# AS3364_DG412_bus_mixer_v1_1.net
KiCad netlist of a schematic drawn in EAGLE
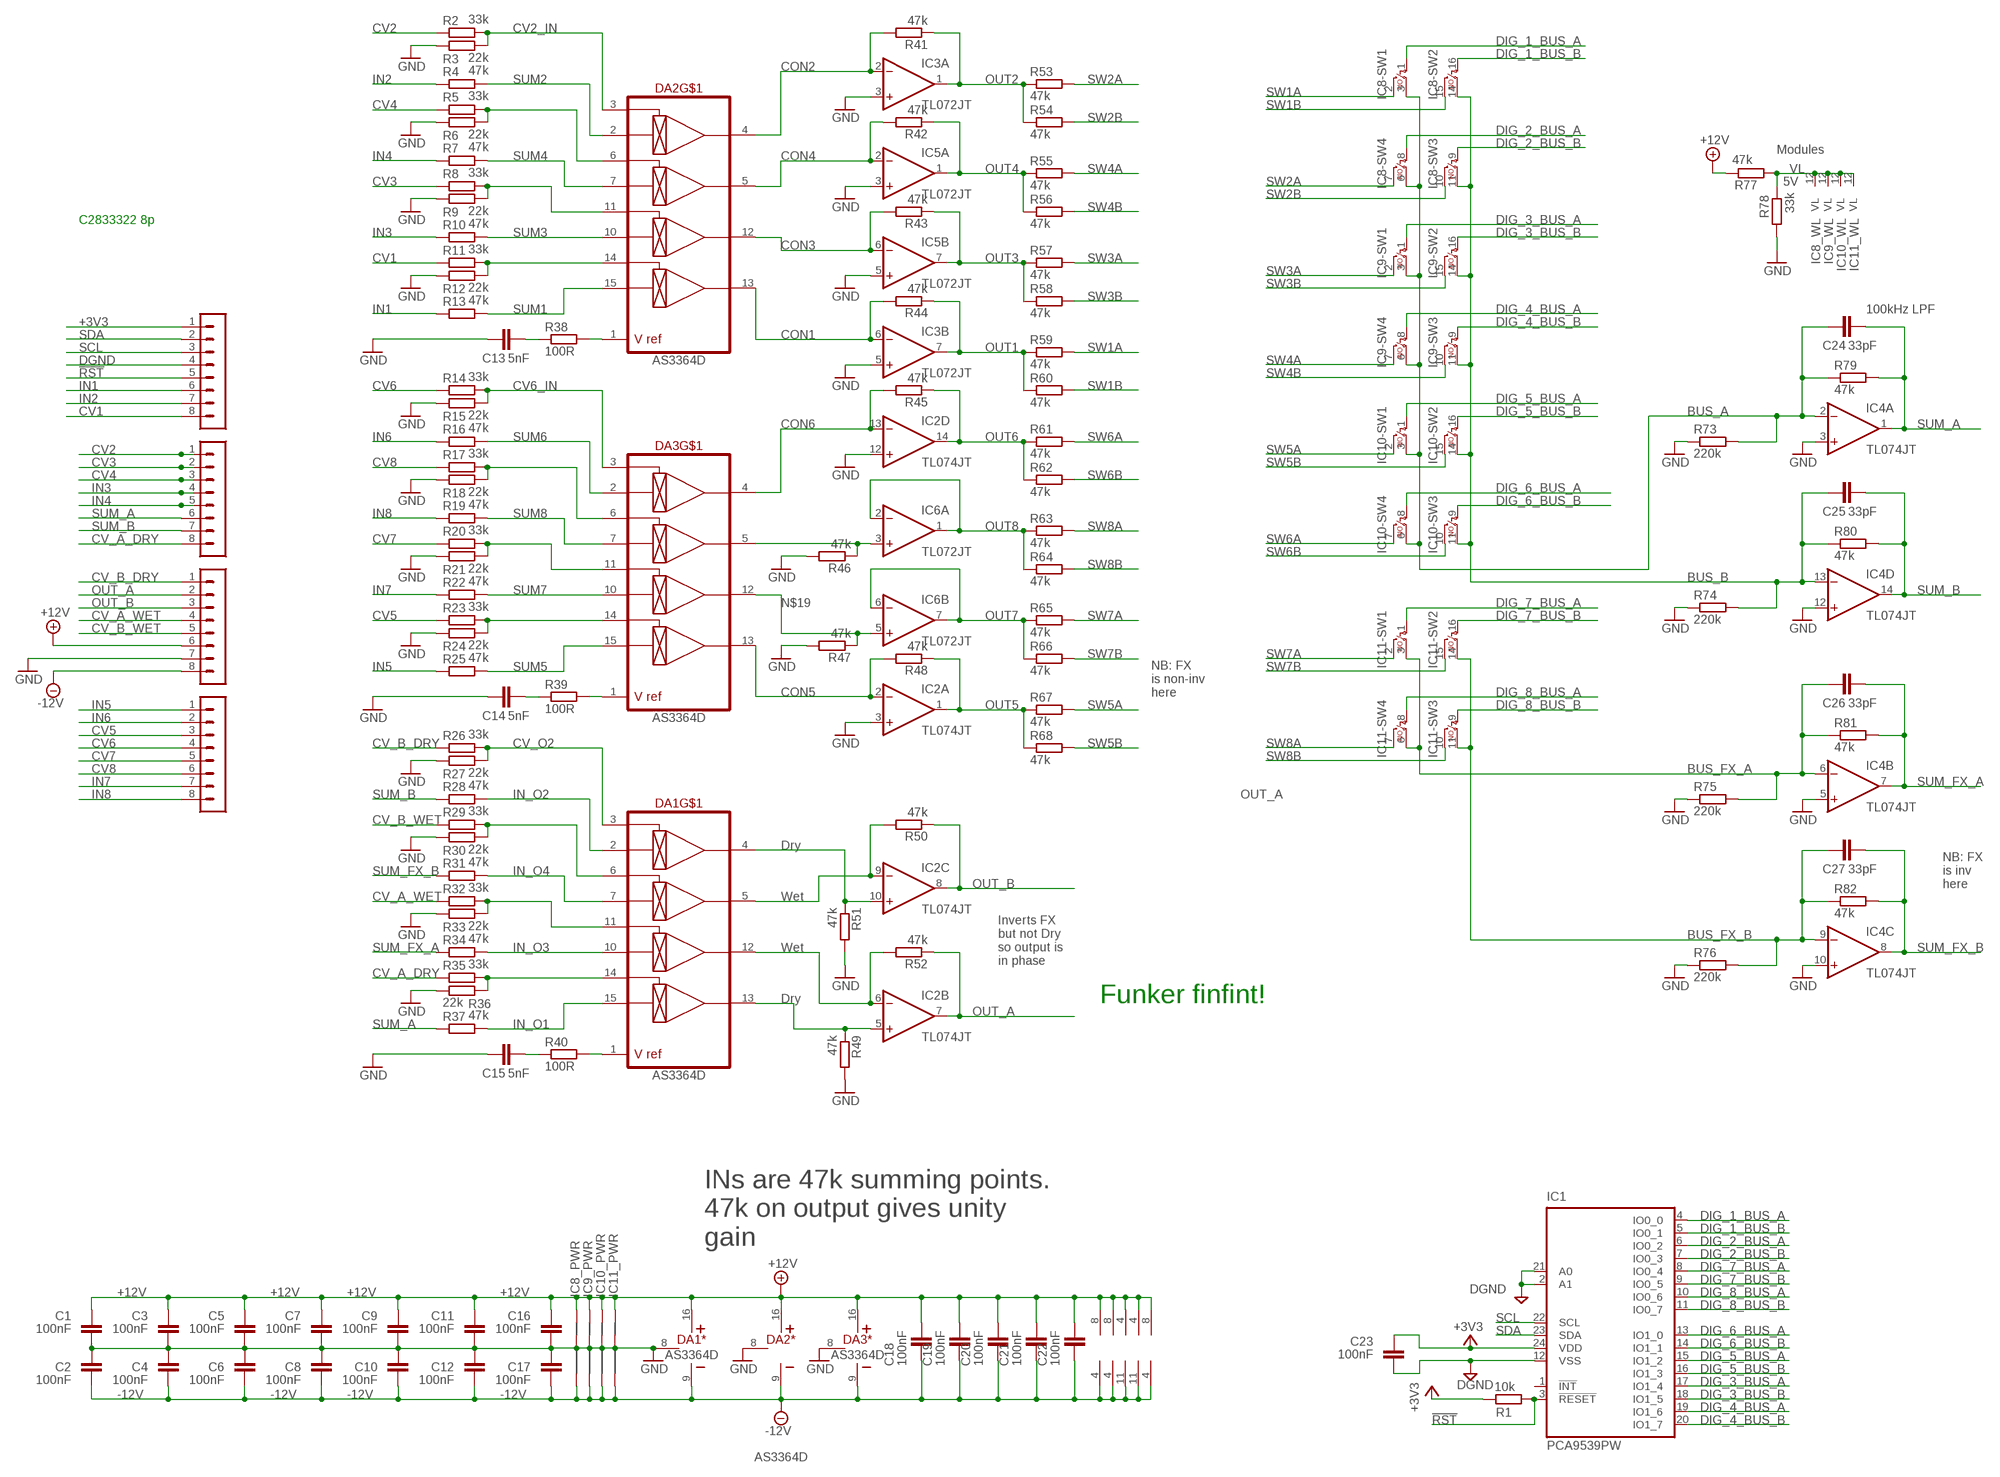
[diagram p0: schematic, sheet 1]

(export (version "E")
  (design (tool "Eeschema 10.0.6"))
  (components
    (comp (ref "C1")
      (value "100nF")
      (footprint "eagle-import:C0402")
      (libsource (lib "eagle-import") (part "C-EUC0402"))
    )
    (comp (ref "C2")
      (value "100nF")
      (footprint "eagle-import:C0402")
      (libsource (lib "eagle-import") (part "C-EUC0402"))
    )
    (comp (ref "C3")
      (value "100nF")
      (footprint "eagle-import:C0402")
      (libsource (lib "eagle-import") (part "C-EUC0402"))
    )
    (comp (ref "C4")
      (value "100nF")
      (footprint "eagle-import:C0402")
      (libsource (lib "eagle-import") (part "C-EUC0402"))
    )
    (comp (ref "C5")
      (value "100nF")
      (footprint "eagle-import:C0402")
      (libsource (lib "eagle-import") (part "C-EUC0402"))
    )
    (comp (ref "C6")
      (value "100nF")
      (footprint "eagle-import:C0402")
      (libsource (lib "eagle-import") (part "C-EUC0402"))
    )
    (comp (ref "C7")
      (value "100nF")
      (footprint "eagle-import:C0402")
      (libsource (lib "eagle-import") (part "C-EUC0402"))
    )
    (comp (ref "C8")
      (value "100nF")
      (footprint "eagle-import:C0402")
      (libsource (lib "eagle-import") (part "C-EUC0402"))
    )
    (comp (ref "C9")
      (value "100nF")
      (footprint "eagle-import:C0402")
      (libsource (lib "eagle-import") (part "C-EUC0402"))
    )
    (comp (ref "C10")
      (value "100nF")
      (footprint "eagle-import:C0402")
      (libsource (lib "eagle-import") (part "C-EUC0402"))
    )
    (comp (ref "C11")
      (value "100nF")
      (footprint "eagle-import:C0402")
      (libsource (lib "eagle-import") (part "C-EUC0402"))
    )
    (comp (ref "C12")
      (value "100nF")
      (footprint "eagle-import:C0402")
      (libsource (lib "eagle-import") (part "C-EUC0402"))
    )
    (comp (ref "C13")
      (value "5nF")
      (footprint "eagle-import:C0402-J")
      (libsource (lib "eagle-import") (part "C-EU-J"))
    )
    (comp (ref "C14")
      (value "5nF")
      (footprint "eagle-import:C0402-J")
      (libsource (lib "eagle-import") (part "C-EU-J"))
    )
    (comp (ref "C15")
      (value "5nF")
      (footprint "eagle-import:C0402-J")
      (libsource (lib "eagle-import") (part "C-EU-J"))
    )
    (comp (ref "C16")
      (value "100nF")
      (footprint "eagle-import:C0402")
      (libsource (lib "eagle-import") (part "C-EUC0402"))
    )
    (comp (ref "C17")
      (value "100nF")
      (footprint "eagle-import:C0402")
      (libsource (lib "eagle-import") (part "C-EUC0402"))
    )
    (comp (ref "C18")
      (value "100nF")
      (footprint "eagle-import:C0402")
      (libsource (lib "eagle-import") (part "C-EUC0402"))
    )
    (comp (ref "C19")
      (value "100nF")
      (footprint "eagle-import:C0402")
      (libsource (lib "eagle-import") (part "C-EUC0402"))
    )
    (comp (ref "C20")
      (value "100nF")
      (footprint "eagle-import:C0402")
      (libsource (lib "eagle-import") (part "C-EUC0402"))
    )
    (comp (ref "C21")
      (value "100nF")
      (footprint "eagle-import:C0402")
      (libsource (lib "eagle-import") (part "C-EUC0402"))
    )
    (comp (ref "C22")
      (value "100nF")
      (footprint "eagle-import:C0402")
      (libsource (lib "eagle-import") (part "C-EUC0402"))
    )
    (comp (ref "C23")
      (value "100nF")
      (footprint "eagle-import:C0402")
      (libsource (lib "eagle-import") (part "C-EUC0402"))
    )
    (comp (ref "C24")
      (value "33pF")
      (footprint "eagle-import:C0402-J")
      (libsource (lib "eagle-import") (part "C-EU-J"))
    )
    (comp (ref "C25")
      (value "33pF")
      (footprint "eagle-import:C0402-J")
      (libsource (lib "eagle-import") (part "C-EU-J"))
    )
    (comp (ref "C26")
      (value "33pF")
      (footprint "eagle-import:C0402-J")
      (libsource (lib "eagle-import") (part "C-EU-J"))
    )
    (comp (ref "C27")
      (value "33pF")
      (footprint "eagle-import:C0402-J")
      (libsource (lib "eagle-import") (part "C-EU-J"))
    )
    (comp (ref "DA1")
      (value "AS3364D")
      (footprint "eagle-import:DIL16J")
      (libsource (lib "eagle-import") (part "AS3364D"))
    )
    (comp (ref "DA2")
      (value "AS3364D")
      (footprint "eagle-import:DIL16J")
      (libsource (lib "eagle-import") (part "AS3364D"))
    )
    (comp (ref "DA3")
      (value "AS3364D")
      (footprint "eagle-import:DIL16J")
      (libsource (lib "eagle-import") (part "AS3364D"))
    )
    (comp (ref "IC1")
      (value "PCA9539PW")
      (footprint "eagle-import:TSSOP24J")
      (libsource (lib "eagle-import") (part "PCA9539PW"))
    )
    (comp (ref "IC2")
      (value "TL074JT")
      (footprint "eagle-import:TSSOP14J")
      (libsource (lib "eagle-import") (part "TL074JT"))
    )
    (comp (ref "IC3")
      (value "TL072JT")
      (footprint "eagle-import:TSSOP8J")
      (libsource (lib "eagle-import") (part "TL072JT"))
    )
    (comp (ref "IC4")
      (value "TL074JT")
      (footprint "eagle-import:TSSOP14J")
      (libsource (lib "eagle-import") (part "TL074JT"))
    )
    (comp (ref "IC5")
      (value "TL072JT")
      (footprint "eagle-import:TSSOP8J")
      (libsource (lib "eagle-import") (part "TL072JT"))
    )
    (comp (ref "IC6")
      (value "TL072JT")
      (footprint "eagle-import:TSSOP8J")
      (libsource (lib "eagle-import") (part "TL072JT"))
    )
    (comp (ref "IC8")
      (value "DG412-J")
      (footprint "eagle-import:DIL16J")
      (libsource (lib "eagle-import") (part "DG412-J"))
    )
    (comp (ref "IC9")
      (value "DG412-J")
      (footprint "eagle-import:DIL16J")
      (libsource (lib "eagle-import") (part "DG412-J"))
    )
    (comp (ref "IC10")
      (value "DG412-J")
      (footprint "eagle-import:DIL16J")
      (libsource (lib "eagle-import") (part "DG412-J"))
    )
    (comp (ref "IC11")
      (value "DG412-J")
      (footprint "eagle-import:DIL16J")
      (libsource (lib "eagle-import") (part "DG412-J"))
    )
    (comp (ref "R1")
      (value "10k")
      (footprint "eagle-import:R0402")
      (libsource (lib "eagle-import") (part "R-EU_R0402"))
    )
    (comp (ref "R2")
      (value "33k")
      (footprint "eagle-import:R0402")
      (libsource (lib "eagle-import") (part "R-EU_R0402"))
    )
    (comp (ref "R3")
      (value "22k")
      (footprint "eagle-import:R0402")
      (libsource (lib "eagle-import") (part "R-EU_R0402"))
    )
    (comp (ref "R4")
      (value "47k")
      (footprint "eagle-import:R0402")
      (libsource (lib "eagle-import") (part "R-EU_R0402"))
    )
    (comp (ref "R5")
      (value "33k")
      (footprint "eagle-import:R0402")
      (libsource (lib "eagle-import") (part "R-EU_R0402"))
    )
    (comp (ref "R6")
      (value "22k")
      (footprint "eagle-import:R0402")
      (libsource (lib "eagle-import") (part "R-EU_R0402"))
    )
    (comp (ref "R7")
      (value "47k")
      (footprint "eagle-import:R0402")
      (libsource (lib "eagle-import") (part "R-EU_R0402"))
    )
    (comp (ref "R8")
      (value "33k")
      (footprint "eagle-import:R0402")
      (libsource (lib "eagle-import") (part "R-EU_R0402"))
    )
    (comp (ref "R9")
      (value "22k")
      (footprint "eagle-import:R0402")
      (libsource (lib "eagle-import") (part "R-EU_R0402"))
    )
    (comp (ref "R10")
      (value "47k")
      (footprint "eagle-import:R0402")
      (libsource (lib "eagle-import") (part "R-EU_R0402"))
    )
    (comp (ref "R11")
      (value "33k")
      (footprint "eagle-import:R0402")
      (libsource (lib "eagle-import") (part "R-EU_R0402"))
    )
    (comp (ref "R12")
      (value "22k")
      (footprint "eagle-import:R0402")
      (libsource (lib "eagle-import") (part "R-EU_R0402"))
    )
    (comp (ref "R13")
      (value "47k")
      (footprint "eagle-import:R0402")
      (libsource (lib "eagle-import") (part "R-EU_R0402"))
    )
    (comp (ref "R14")
      (value "33k")
      (footprint "eagle-import:R0402")
      (libsource (lib "eagle-import") (part "R-EU_R0402"))
    )
    (comp (ref "R15")
      (value "22k")
      (footprint "eagle-import:R0402")
      (libsource (lib "eagle-import") (part "R-EU_R0402"))
    )
    (comp (ref "R16")
      (value "47k")
      (footprint "eagle-import:R0402")
      (libsource (lib "eagle-import") (part "R-EU_R0402"))
    )
    (comp (ref "R17")
      (value "33k")
      (footprint "eagle-import:R0402")
      (libsource (lib "eagle-import") (part "R-EU_R0402"))
    )
    (comp (ref "R18")
      (value "22k")
      (footprint "eagle-import:R0402")
      (libsource (lib "eagle-import") (part "R-EU_R0402"))
    )
    (comp (ref "R19")
      (value "47k")
      (footprint "eagle-import:R0402")
      (libsource (lib "eagle-import") (part "R-EU_R0402"))
    )
    (comp (ref "R20")
      (value "33k")
      (footprint "eagle-import:R0402")
      (libsource (lib "eagle-import") (part "R-EU_R0402"))
    )
    (comp (ref "R21")
      (value "22k")
      (footprint "eagle-import:R0402")
      (libsource (lib "eagle-import") (part "R-EU_R0402"))
    )
    (comp (ref "R22")
      (value "47k")
      (footprint "eagle-import:R0402")
      (libsource (lib "eagle-import") (part "R-EU_R0402"))
    )
    (comp (ref "R23")
      (value "33k")
      (footprint "eagle-import:R0402")
      (libsource (lib "eagle-import") (part "R-EU_R0402"))
    )
    (comp (ref "R24")
      (value "22k")
      (footprint "eagle-import:R0402")
      (libsource (lib "eagle-import") (part "R-EU_R0402"))
    )
    (comp (ref "R25")
      (value "47k")
      (footprint "eagle-import:R0402")
      (libsource (lib "eagle-import") (part "R-EU_R0402"))
    )
    (comp (ref "R26")
      (value "33k")
      (footprint "eagle-import:R0402")
      (libsource (lib "eagle-import") (part "R-EU_R0402"))
    )
    (comp (ref "R27")
      (value "22k")
      (footprint "eagle-import:R0402")
      (libsource (lib "eagle-import") (part "R-EU_R0402"))
    )
    (comp (ref "R28")
      (value "47k")
      (footprint "eagle-import:R0402")
      (libsource (lib "eagle-import") (part "R-EU_R0402"))
    )
    (comp (ref "R29")
      (value "33k")
      (footprint "eagle-import:R0402")
      (libsource (lib "eagle-import") (part "R-EU_R0402"))
    )
    (comp (ref "R30")
      (value "22k")
      (footprint "eagle-import:R0402")
      (libsource (lib "eagle-import") (part "R-EU_R0402"))
    )
    (comp (ref "R31")
      (value "47k")
      (footprint "eagle-import:R0402")
      (libsource (lib "eagle-import") (part "R-EU_R0402"))
    )
    (comp (ref "R32")
      (value "33k")
      (footprint "eagle-import:R0402")
      (libsource (lib "eagle-import") (part "R-EU_R0402"))
    )
    (comp (ref "R33")
      (value "22k")
      (footprint "eagle-import:R0402")
      (libsource (lib "eagle-import") (part "R-EU_R0402"))
    )
    (comp (ref "R34")
      (value "47k")
      (footprint "eagle-import:R0402")
      (libsource (lib "eagle-import") (part "R-EU_R0402"))
    )
    (comp (ref "R35")
      (value "33k")
      (footprint "eagle-import:R0402")
      (libsource (lib "eagle-import") (part "R-EU_R0402"))
    )
    (comp (ref "R36")
      (value "22k")
      (footprint "eagle-import:R0402")
      (libsource (lib "eagle-import") (part "R-EU_R0402"))
    )
    (comp (ref "R37")
      (value "47k")
      (footprint "eagle-import:R0402")
      (libsource (lib "eagle-import") (part "R-EU_R0402"))
    )
    (comp (ref "R38")
      (value "100R")
      (footprint "eagle-import:R0402")
      (libsource (lib "eagle-import") (part "R-EU_R0402"))
    )
    (comp (ref "R39")
      (value "100R")
      (footprint "eagle-import:R0402")
      (libsource (lib "eagle-import") (part "R-EU_R0402"))
    )
    (comp (ref "R40")
      (value "100R")
      (footprint "eagle-import:R0402")
      (libsource (lib "eagle-import") (part "R-EU_R0402"))
    )
    (comp (ref "R41")
      (value "47k")
      (footprint "eagle-import:R0402")
      (libsource (lib "eagle-import") (part "R-EU_R0402"))
    )
    (comp (ref "R42")
      (value "47k")
      (footprint "eagle-import:R0402")
      (libsource (lib "eagle-import") (part "R-EU_R0402"))
    )
    (comp (ref "R43")
      (value "47k")
      (footprint "eagle-import:R0402")
      (libsource (lib "eagle-import") (part "R-EU_R0402"))
    )
    (comp (ref "R44")
      (value "47k")
      (footprint "eagle-import:R0402")
      (libsource (lib "eagle-import") (part "R-EU_R0402"))
    )
    (comp (ref "R45")
      (value "47k")
      (footprint "eagle-import:R0402")
      (libsource (lib "eagle-import") (part "R-EU_R0402"))
    )
    (comp (ref "R46")
      (value "47k")
      (footprint "eagle-import:R0402")
      (libsource (lib "eagle-import") (part "R-EU_R0402"))
    )
    (comp (ref "R47")
      (value "47k")
      (footprint "eagle-import:R0402")
      (libsource (lib "eagle-import") (part "R-EU_R0402"))
    )
    (comp (ref "R48")
      (value "47k")
      (footprint "eagle-import:R0402")
      (libsource (lib "eagle-import") (part "R-EU_R0402"))
    )
    (comp (ref "R49")
      (value "47k")
      (footprint "eagle-import:R0402")
      (libsource (lib "eagle-import") (part "R-EU_R0402"))
    )
    (comp (ref "R50")
      (value "47k")
      (footprint "eagle-import:R0402")
      (libsource (lib "eagle-import") (part "R-EU_R0402"))
    )
    (comp (ref "R51")
      (value "47k")
      (footprint "eagle-import:R0402")
      (libsource (lib "eagle-import") (part "R-EU_R0402"))
    )
    (comp (ref "R52")
      (value "47k")
      (footprint "eagle-import:R0402")
      (libsource (lib "eagle-import") (part "R-EU_R0402"))
    )
    (comp (ref "R53")
      (value "47k")
      (footprint "eagle-import:R0402")
      (libsource (lib "eagle-import") (part "R-EU_R0402"))
    )
    (comp (ref "R54")
      (value "47k")
      (footprint "eagle-import:R0402")
      (libsource (lib "eagle-import") (part "R-EU_R0402"))
    )
    (comp (ref "R55")
      (value "47k")
      (footprint "eagle-import:R0402")
      (libsource (lib "eagle-import") (part "R-EU_R0402"))
    )
    (comp (ref "R56")
      (value "47k")
      (footprint "eagle-import:R0402")
      (libsource (lib "eagle-import") (part "R-EU_R0402"))
    )
    (comp (ref "R57")
      (value "47k")
      (footprint "eagle-import:R0402")
      (libsource (lib "eagle-import") (part "R-EU_R0402"))
    )
    (comp (ref "R58")
      (value "47k")
      (footprint "eagle-import:R0402")
      (libsource (lib "eagle-import") (part "R-EU_R0402"))
    )
    (comp (ref "R59")
      (value "47k")
      (footprint "eagle-import:R0402")
      (libsource (lib "eagle-import") (part "R-EU_R0402"))
    )
    (comp (ref "R60")
      (value "47k")
      (footprint "eagle-import:R0402")
      (libsource (lib "eagle-import") (part "R-EU_R0402"))
    )
    (comp (ref "R61")
      (value "47k")
      (footprint "eagle-import:R0402")
      (libsource (lib "eagle-import") (part "R-EU_R0402"))
    )
    (comp (ref "R62")
      (value "47k")
      (footprint "eagle-import:R0402")
      (libsource (lib "eagle-import") (part "R-EU_R0402"))
    )
    (comp (ref "R63")
      (value "47k")
      (footprint "eagle-import:R0402")
      (libsource (lib "eagle-import") (part "R-EU_R0402"))
    )
    (comp (ref "R64")
      (value "47k")
      (footprint "eagle-import:R0402")
      (libsource (lib "eagle-import") (part "R-EU_R0402"))
    )
    (comp (ref "R65")
      (value "47k")
      (footprint "eagle-import:R0402")
      (libsource (lib "eagle-import") (part "R-EU_R0402"))
    )
    (comp (ref "R66")
      (value "47k")
      (footprint "eagle-import:R0402")
      (libsource (lib "eagle-import") (part "R-EU_R0402"))
    )
    (comp (ref "R67")
      (value "47k")
      (footprint "eagle-import:R0402")
      (libsource (lib "eagle-import") (part "R-EU_R0402"))
    )
    (comp (ref "R68")
      (value "47k")
      (footprint "eagle-import:R0402")
      (libsource (lib "eagle-import") (part "R-EU_R0402"))
    )
    (comp (ref "R73")
      (value "220k")
      (footprint "eagle-import:R0402")
      (libsource (lib "eagle-import") (part "R-EU_R0402"))
    )
    (comp (ref "R74")
      (value "220k")
      (footprint "eagle-import:R0402")
      (libsource (lib "eagle-import") (part "R-EU_R0402"))
    )
    (comp (ref "R75")
      (value "220k")
      (footprint "eagle-import:R0402")
      (libsource (lib "eagle-import") (part "R-EU_R0402"))
    )
    (comp (ref "R76")
      (value "220k")
      (footprint "eagle-import:R0402")
      (libsource (lib "eagle-import") (part "R-EU_R0402"))
    )
    (comp (ref "R77")
      (value "47k")
      (footprint "eagle-import:R0402")
      (libsource (lib "eagle-import") (part "R-EU_R0402"))
    )
    (comp (ref "R78")
      (value "33k")
      (footprint "eagle-import:R0402")
      (libsource (lib "eagle-import") (part "R-EU_R0402"))
    )
    (comp (ref "R79")
      (value "47k")
      (footprint "eagle-import:R0402")
      (libsource (lib "eagle-import") (part "R-EU_R0402"))
    )
    (comp (ref "R80")
      (value "47k")
      (footprint "eagle-import:R0402")
      (libsource (lib "eagle-import") (part "R-EU_R0402"))
    )
    (comp (ref "R81")
      (value "47k")
      (footprint "eagle-import:R0402")
      (libsource (lib "eagle-import") (part "R-EU_R0402"))
    )
    (comp (ref "R82")
      (value "47k")
      (footprint "eagle-import:R0402")
      (libsource (lib "eagle-import") (part "R-EU_R0402"))
    )
    (comp (ref "SV1")
      (value "MA08-1JP")
      (footprint "eagle-import:SIP-PIN08-1J")
      (libsource (lib "eagle-import") (part "MA08-1JP"))
    )
    (comp (ref "SV3")
      (value "MA08-1JP")
      (footprint "eagle-import:SIP-PIN08-1J")
      (libsource (lib "eagle-import") (part "MA08-1JP"))
    )
    (comp (ref "SV4")
      (value "MA08-1JP")
      (footprint "eagle-import:SIP-PIN08-1J")
      (libsource (lib "eagle-import") (part "MA08-1JP"))
    )
    (comp (ref "SV33")
      (value "MA08-1JP")
      (footprint "eagle-import:SIP-PIN08-1J")
      (libsource (lib "eagle-import") (part "MA08-1JP"))
    )
  )
  (nets
    (net (code "1") (name "+3V3") (class "Default")
      (node (ref "C23") (pin "2") (pinfunction "2_2") (pintype "passive"))
      (node (ref "IC1") (pin "24") (pinfunction "VDD_24") (pintype "power_in"))
      (node (ref "R1") (pin "1") (pinfunction "1_1") (pintype "passive"))
      (node (ref "SV33") (pin "1") (pinfunction "1_1") (pintype "passive"))
    )
    (net (code "2") (name "+12V") (class "Default")
      (node (ref "C1") (pin "2") (pinfunction "2_2") (pintype "passive"))
      (node (ref "C11") (pin "2") (pinfunction "2_2") (pintype "passive"))
      (node (ref "C16") (pin "2") (pinfunction "2_2") (pintype "passive"))
      (node (ref "C18") (pin "2") (pinfunction "2_2") (pintype "passive"))
      (node (ref "C19") (pin "2") (pinfunction "2_2") (pintype "passive"))
      (node (ref "C20") (pin "2") (pinfunction "2_2") (pintype "passive"))
      (node (ref "C21") (pin "2") (pinfunction "2_2") (pintype "passive"))
      (node (ref "C22") (pin "2") (pinfunction "2_2") (pintype "passive"))
      (node (ref "C3") (pin "2") (pinfunction "2_2") (pintype "passive"))
      (node (ref "C5") (pin "2") (pinfunction "2_2") (pintype "passive"))
      (node (ref "C7") (pin "2") (pinfunction "2_2") (pintype "passive"))
      (node (ref "C9") (pin "2") (pinfunction "2_2") (pintype "passive"))
      (node (ref "DA1") (pin "16") (pinfunction "V+_16") (pintype "power_in"))
      (node (ref "DA2") (pin "16") (pinfunction "V+_16") (pintype "power_in"))
      (node (ref "DA3") (pin "16") (pinfunction "V+_16") (pintype "power_in"))
      (node (ref "IC10") (pin "13") (pinfunction "+15V_13") (pintype "power_in"))
      (node (ref "IC11") (pin "13") (pinfunction "+15V_13") (pintype "power_in"))
      (node (ref "IC2") (pin "4") (pinfunction "V+_4") (pintype "power_in"))
      (node (ref "IC3") (pin "8") (pinfunction "V+_8") (pintype "power_in"))
      (node (ref "IC4") (pin "4") (pinfunction "V+_4") (pintype "power_in"))
      (node (ref "IC5") (pin "8") (pinfunction "V+_8") (pintype "power_in"))
      (node (ref "IC6") (pin "8") (pinfunction "V+_8") (pintype "power_in"))
      (node (ref "IC8") (pin "13") (pinfunction "+15V_13") (pintype "power_in"))
      (node (ref "IC9") (pin "13") (pinfunction "+15V_13") (pintype "power_in"))
      (node (ref "R77") (pin "1") (pinfunction "1_1") (pintype "passive"))
      (node (ref "SV4") (pin "6") (pinfunction "6_6") (pintype "passive"))
    )
    (net (code "3") (name "-12V") (class "Default")
      (node (ref "C10") (pin "1") (pinfunction "1_1") (pintype "passive"))
      (node (ref "C12") (pin "1") (pinfunction "1_1") (pintype "passive"))
      (node (ref "C17") (pin "1") (pinfunction "1_1") (pintype "passive"))
      (node (ref "C18") (pin "1") (pinfunction "1_1") (pintype "passive"))
      (node (ref "C19") (pin "1") (pinfunction "1_1") (pintype "passive"))
      (node (ref "C2") (pin "1") (pinfunction "1_1") (pintype "passive"))
      (node (ref "C20") (pin "1") (pinfunction "1_1") (pintype "passive"))
      (node (ref "C21") (pin "1") (pinfunction "1_1") (pintype "passive"))
      (node (ref "C22") (pin "1") (pinfunction "1_1") (pintype "passive"))
      (node (ref "C4") (pin "1") (pinfunction "1_1") (pintype "passive"))
      (node (ref "C6") (pin "1") (pinfunction "1_1") (pintype "passive"))
      (node (ref "C8") (pin "1") (pinfunction "1_1") (pintype "passive"))
      (node (ref "DA1") (pin "9") (pinfunction "V-_9") (pintype "power_in"))
      (node (ref "DA2") (pin "9") (pinfunction "V-_9") (pintype "power_in"))
      (node (ref "DA3") (pin "9") (pinfunction "V-_9") (pintype "power_in"))
      (node (ref "IC10") (pin "4") (pinfunction "-15V_4") (pintype "power_in"))
      (node (ref "IC11") (pin "4") (pinfunction "-15V_4") (pintype "power_in"))
      (node (ref "IC2") (pin "11") (pinfunction "V-_11") (pintype "power_in"))
      (node (ref "IC3") (pin "4") (pinfunction "V-_4") (pintype "power_in"))
      (node (ref "IC4") (pin "11") (pinfunction "V-_11") (pintype "power_in"))
      (node (ref "IC5") (pin "4") (pinfunction "V-_4") (pintype "power_in"))
      (node (ref "IC6") (pin "4") (pinfunction "V-_4") (pintype "power_in"))
      (node (ref "IC8") (pin "4") (pinfunction "-15V_4") (pintype "power_in"))
      (node (ref "IC9") (pin "4") (pinfunction "-15V_4") (pintype "power_in"))
      (node (ref "SV4") (pin "8") (pinfunction "8_8") (pintype "passive"))
    )
    (net (code "4") (name "/BUS_A") (class "Default")
      (node (ref "C24") (pin "1") (pinfunction "1_1") (pintype "passive"))
      (node (ref "IC10") (pin "3") (pinfunction "S_3") (pintype "bidirectional"))
      (node (ref "IC10") (pin "6") (pinfunction "S_6") (pintype "bidirectional"))
      (node (ref "IC4") (pin "2") (pinfunction "-IN_2") (pintype "input"))
      (node (ref "IC8") (pin "3") (pinfunction "S_3") (pintype "bidirectional"))
      (node (ref "IC8") (pin "6") (pinfunction "S_6") (pintype "bidirectional"))
      (node (ref "IC9") (pin "3") (pinfunction "S_3") (pintype "bidirectional"))
      (node (ref "IC9") (pin "6") (pinfunction "S_6") (pintype "bidirectional"))
      (node (ref "R73") (pin "2") (pinfunction "2_2") (pintype "passive"))
      (node (ref "R79") (pin "1") (pinfunction "1_1") (pintype "passive"))
    )
    (net (code "5") (name "/BUS_B") (class "Default")
      (node (ref "C25") (pin "1") (pinfunction "1_1") (pintype "passive"))
      (node (ref "IC10") (pin "11") (pinfunction "S_11") (pintype "bidirectional"))
      (node (ref "IC10") (pin "14") (pinfunction "S_14") (pintype "bidirectional"))
      (node (ref "IC4") (pin "13") (pinfunction "-IN_13") (pintype "input"))
      (node (ref "IC8") (pin "11") (pinfunction "S_11") (pintype "bidirectional"))
      (node (ref "IC8") (pin "14") (pinfunction "S_14") (pintype "bidirectional"))
      (node (ref "IC9") (pin "11") (pinfunction "S_11") (pintype "bidirectional"))
      (node (ref "IC9") (pin "14") (pinfunction "S_14") (pintype "bidirectional"))
      (node (ref "R74") (pin "2") (pinfunction "2_2") (pintype "passive"))
      (node (ref "R80") (pin "1") (pinfunction "1_1") (pintype "passive"))
    )
    (net (code "6") (name "/BUS_FX_A") (class "Default")
      (node (ref "C26") (pin "1") (pinfunction "1_1") (pintype "passive"))
      (node (ref "IC11") (pin "3") (pinfunction "S_3") (pintype "bidirectional"))
      (node (ref "IC11") (pin "6") (pinfunction "S_6") (pintype "bidirectional"))
      (node (ref "IC4") (pin "6") (pinfunction "-IN_6") (pintype "input"))
      (node (ref "R75") (pin "2") (pinfunction "2_2") (pintype "passive"))
      (node (ref "R81") (pin "1") (pinfunction "1_1") (pintype "passive"))
    )
    (net (code "7") (name "/BUS_FX_B") (class "Default")
      (node (ref "C27") (pin "1") (pinfunction "1_1") (pintype "passive"))
      (node (ref "IC11") (pin "11") (pinfunction "S_11") (pintype "bidirectional"))
      (node (ref "IC11") (pin "14") (pinfunction "S_14") (pintype "bidirectional"))
      (node (ref "IC4") (pin "9") (pinfunction "-IN_9") (pintype "input"))
      (node (ref "R76") (pin "2") (pinfunction "2_2") (pintype "passive"))
      (node (ref "R82") (pin "1") (pinfunction "1_1") (pintype "passive"))
    )
    (net (code "8") (name "/CON1") (class "Default")
      (node (ref "DA2") (pin "13") (pinfunction "OUT4_13") (pintype "output"))
      (node (ref "IC3") (pin "6") (pinfunction "-IN_6") (pintype "input"))
      (node (ref "R44") (pin "2") (pinfunction "2_2") (pintype "passive"))
    )
    (net (code "9") (name "/CON2") (class "Default")
      (node (ref "DA2") (pin "4") (pinfunction "OUT1_4") (pintype "output"))
      (node (ref "IC3") (pin "2") (pinfunction "-IN_2") (pintype "input"))
      (node (ref "R41") (pin "2") (pinfunction "2_2") (pintype "passive"))
    )
    (net (code "10") (name "/CON3") (class "Default")
      (node (ref "DA2") (pin "12") (pinfunction "OUT3_12") (pintype "output"))
      (node (ref "IC5") (pin "6") (pinfunction "-IN_6") (pintype "input"))
      (node (ref "R43") (pin "2") (pinfunction "2_2") (pintype "passive"))
    )
    (net (code "11") (name "/CON4") (class "Default")
      (node (ref "DA2") (pin "5") (pinfunction "OUT2_5") (pintype "output"))
      (node (ref "IC5") (pin "2") (pinfunction "-IN_2") (pintype "input"))
      (node (ref "R42") (pin "2") (pinfunction "2_2") (pintype "passive"))
    )
    (net (code "12") (name "/CON5") (class "Default")
      (node (ref "DA3") (pin "13") (pinfunction "OUT4_13") (pintype "output"))
      (node (ref "IC2") (pin "2") (pinfunction "-IN_2") (pintype "input"))
      (node (ref "R48") (pin "2") (pinfunction "2_2") (pintype "passive"))
    )
    (net (code "13") (name "/CON6") (class "Default")
      (node (ref "DA3") (pin "4") (pinfunction "OUT1_4") (pintype "output"))
      (node (ref "IC2") (pin "13") (pinfunction "-IN_13") (pintype "input"))
      (node (ref "R45") (pin "2") (pinfunction "2_2") (pintype "passive"))
    )
    (net (code "14") (name "/CV1") (class "Default")
      (node (ref "R11") (pin "1") (pinfunction "1_1") (pintype "passive"))
      (node (ref "SV33") (pin "8") (pinfunction "8_8") (pintype "passive"))
    )
    (net (code "15") (name "/CV2") (class "Default")
      (node (ref "R2") (pin "1") (pinfunction "1_1") (pintype "passive"))
      (node (ref "SV1") (pin "1") (pinfunction "1_1") (pintype "passive"))
    )
    (net (code "16") (name "/CV2_IN") (class "Default")
      (node (ref "DA2") (pin "3") (pinfunction "CV1_3") (pintype "input"))
      (node (ref "R2") (pin "2") (pinfunction "2_2") (pintype "passive"))
      (node (ref "R3") (pin "2") (pinfunction "2_2") (pintype "passive"))
    )
    (net (code "17") (name "/CV3") (class "Default")
      (node (ref "R8") (pin "1") (pinfunction "1_1") (pintype "passive"))
      (node (ref "SV1") (pin "2") (pinfunction "2_2") (pintype "passive"))
    )
    (net (code "18") (name "/CV4") (class "Default")
      (node (ref "R5") (pin "1") (pinfunction "1_1") (pintype "passive"))
      (node (ref "SV1") (pin "3") (pinfunction "3_3") (pintype "passive"))
    )
    (net (code "19") (name "/CV5") (class "Default")
      (node (ref "R23") (pin "1") (pinfunction "1_1") (pintype "passive"))
      (node (ref "SV3") (pin "3") (pinfunction "3_3") (pintype "passive"))
    )
    (net (code "20") (name "/CV6") (class "Default")
      (node (ref "R14") (pin "1") (pinfunction "1_1") (pintype "passive"))
      (node (ref "SV3") (pin "4") (pinfunction "4_4") (pintype "passive"))
    )
    (net (code "21") (name "/CV6_IN") (class "Default")
      (node (ref "DA3") (pin "3") (pinfunction "CV1_3") (pintype "input"))
      (node (ref "R14") (pin "2") (pinfunction "2_2") (pintype "passive"))
      (node (ref "R15") (pin "2") (pinfunction "2_2") (pintype "passive"))
    )
    (net (code "22") (name "/CV7") (class "Default")
      (node (ref "R20") (pin "1") (pinfunction "1_1") (pintype "passive"))
      (node (ref "SV3") (pin "5") (pinfunction "5_5") (pintype "passive"))
    )
    (net (code "23") (name "/CV8") (class "Default")
      (node (ref "R17") (pin "1") (pinfunction "1_1") (pintype "passive"))
      (node (ref "SV3") (pin "6") (pinfunction "6_6") (pintype "passive"))
    )
    (net (code "24") (name "/CV_A_DRY") (class "Default")
      (node (ref "R35") (pin "1") (pinfunction "1_1") (pintype "passive"))
      (node (ref "SV1") (pin "8") (pinfunction "8_8") (pintype "passive"))
    )
    (net (code "25") (name "/CV_A_WET") (class "Default")
      (node (ref "R32") (pin "1") (pinfunction "1_1") (pintype "passive"))
      (node (ref "SV4") (pin "4") (pinfunction "4_4") (pintype "passive"))
    )
    (net (code "26") (name "/CV_B_DRY") (class "Default")
      (node (ref "R26") (pin "1") (pinfunction "1_1") (pintype "passive"))
      (node (ref "SV4") (pin "1") (pinfunction "1_1") (pintype "passive"))
    )
    (net (code "27") (name "/CV_B_WET") (class "Default")
      (node (ref "R29") (pin "1") (pinfunction "1_1") (pintype "passive"))
      (node (ref "SV4") (pin "5") (pinfunction "5_5") (pintype "passive"))
    )
    (net (code "28") (name "/CV_O2") (class "Default")
      (node (ref "DA1") (pin "3") (pinfunction "CV1_3") (pintype "input"))
      (node (ref "R26") (pin "2") (pinfunction "2_2") (pintype "passive"))
      (node (ref "R27") (pin "2") (pinfunction "2_2") (pintype "passive"))
    )
    (net (code "29") (name "/DIG_1_BUS_A") (class "Default")
      (node (ref "IC1") (pin "4") (pinfunction "IO0_0_4") (pintype "bidirectional"))
      (node (ref "IC8") (pin "1") (pinfunction "C_1") (pintype "bidirectional"))
    )
    (net (code "30") (name "/DIG_1_BUS_B") (class "Default")
      (node (ref "IC1") (pin "5") (pinfunction "IO0_1_5") (pintype "bidirectional"))
      (node (ref "IC8") (pin "16") (pinfunction "C_16") (pintype "bidirectional"))
    )
    (net (code "31") (name "/DIG_2_BUS_A") (class "Default")
      (node (ref "IC1") (pin "6") (pinfunction "IO0_2_6") (pintype "bidirectional"))
      (node (ref "IC8") (pin "8") (pinfunction "C_8") (pintype "bidirectional"))
    )
    (net (code "32") (name "/DIG_2_BUS_B") (class "Default")
      (node (ref "IC1") (pin "7") (pinfunction "IO0_3_7") (pintype "bidirectional"))
      (node (ref "IC8") (pin "9") (pinfunction "C_9") (pintype "bidirectional"))
    )
    (net (code "33") (name "/DIG_3_BUS_A") (class "Default")
      (node (ref "IC1") (pin "17") (pinfunction "IO1_4_17") (pintype "bidirectional"))
      (node (ref "IC9") (pin "1") (pinfunction "C_1") (pintype "bidirectional"))
    )
    (net (code "34") (name "/DIG_3_BUS_B") (class "Default")
      (node (ref "IC1") (pin "18") (pinfunction "IO1_5_18") (pintype "bidirectional"))
      (node (ref "IC9") (pin "16") (pinfunction "C_16") (pintype "bidirectional"))
    )
    (net (code "35") (name "/DIG_4_BUS_A") (class "Default")
      (node (ref "IC1") (pin "19") (pinfunction "IO1_6_19") (pintype "bidirectional"))
      (node (ref "IC9") (pin "8") (pinfunction "C_8") (pintype "bidirectional"))
    )
    (net (code "36") (name "/DIG_4_BUS_B") (class "Default")
      (node (ref "IC1") (pin "20") (pinfunction "IO1_7_20") (pintype "bidirectional"))
      (node (ref "IC9") (pin "9") (pinfunction "C_9") (pintype "bidirectional"))
    )
    (net (code "37") (name "/DIG_5_BUS_A") (class "Default")
      (node (ref "IC1") (pin "15") (pinfunction "IO1_2_15") (pintype "bidirectional"))
      (node (ref "IC10") (pin "1") (pinfunction "C_1") (pintype "bidirectional"))
    )
    (net (code "38") (name "/DIG_5_BUS_B") (class "Default")
      (node (ref "IC1") (pin "16") (pinfunction "IO1_3_16") (pintype "bidirectional"))
      (node (ref "IC10") (pin "16") (pinfunction "C_16") (pintype "bidirectional"))
    )
    (net (code "39") (name "/DIG_6_BUS_A") (class "Default")
      (node (ref "IC1") (pin "13") (pinfunction "IO1_0_13") (pintype "bidirectional"))
      (node (ref "IC10") (pin "8") (pinfunction "C_8") (pintype "bidirectional"))
    )
    (net (code "40") (name "/DIG_6_BUS_B") (class "Default")
      (node (ref "IC1") (pin "14") (pinfunction "IO1_1_14") (pintype "bidirectional"))
      (node (ref "IC10") (pin "9") (pinfunction "C_9") (pintype "bidirectional"))
    )
    (net (code "41") (name "/DIG_7_BUS_A") (class "Default")
      (node (ref "IC1") (pin "8") (pinfunction "IO0_4_8") (pintype "bidirectional"))
      (node (ref "IC11") (pin "1") (pinfunction "C_1") (pintype "bidirectional"))
    )
    (net (code "42") (name "/DIG_7_BUS_B") (class "Default")
      (node (ref "IC1") (pin "9") (pinfunction "IO0_5_9") (pintype "bidirectional"))
      (node (ref "IC11") (pin "16") (pinfunction "C_16") (pintype "bidirectional"))
    )
    (net (code "43") (name "/DIG_8_BUS_A") (class "Default")
      (node (ref "IC1") (pin "10") (pinfunction "IO0_6_10") (pintype "bidirectional"))
      (node (ref "IC11") (pin "8") (pinfunction "C_8") (pintype "bidirectional"))
    )
    (net (code "44") (name "/DIG_8_BUS_B") (class "Default")
      (node (ref "IC1") (pin "11") (pinfunction "IO0_7_11") (pintype "bidirectional"))
      (node (ref "IC11") (pin "9") (pinfunction "C_9") (pintype "bidirectional"))
    )
    (net (code "45") (name "/IN1") (class "Default")
      (node (ref "R13") (pin "1") (pinfunction "1_1") (pintype "passive"))
      (node (ref "SV33") (pin "6") (pinfunction "6_6") (pintype "passive"))
    )
    (net (code "46") (name "/IN2") (class "Default")
      (node (ref "R4") (pin "1") (pinfunction "1_1") (pintype "passive"))
      (node (ref "SV33") (pin "7") (pinfunction "7_7") (pintype "passive"))
    )
    (net (code "47") (name "/IN3") (class "Default")
      (node (ref "R10") (pin "1") (pinfunction "1_1") (pintype "passive"))
      (node (ref "SV1") (pin "4") (pinfunction "4_4") (pintype "passive"))
    )
    (net (code "48") (name "/IN4") (class "Default")
      (node (ref "R7") (pin "1") (pinfunction "1_1") (pintype "passive"))
      (node (ref "SV1") (pin "5") (pinfunction "5_5") (pintype "passive"))
    )
    (net (code "49") (name "/IN5") (class "Default")
      (node (ref "R25") (pin "1") (pinfunction "1_1") (pintype "passive"))
      (node (ref "SV3") (pin "1") (pinfunction "1_1") (pintype "passive"))
    )
    (net (code "50") (name "/IN6") (class "Default")
      (node (ref "R16") (pin "1") (pinfunction "1_1") (pintype "passive"))
      (node (ref "SV3") (pin "2") (pinfunction "2_2") (pintype "passive"))
    )
    (net (code "51") (name "/IN7") (class "Default")
      (node (ref "R22") (pin "1") (pinfunction "1_1") (pintype "passive"))
      (node (ref "SV3") (pin "7") (pinfunction "7_7") (pintype "passive"))
    )
    (net (code "52") (name "/IN8") (class "Default")
      (node (ref "R19") (pin "1") (pinfunction "1_1") (pintype "passive"))
      (node (ref "SV3") (pin "8") (pinfunction "8_8") (pintype "passive"))
    )
    (net (code "53") (name "/IN_O1") (class "Default")
      (node (ref "DA1") (pin "15") (pinfunction "IN4_15") (pintype "input"))
      (node (ref "R37") (pin "2") (pinfunction "2_2") (pintype "passive"))
    )
    (net (code "54") (name "/IN_O2") (class "Default")
      (node (ref "DA1") (pin "2") (pinfunction "IN1_2") (pintype "input"))
      (node (ref "R28") (pin "2") (pinfunction "2_2") (pintype "passive"))
    )
    (net (code "55") (name "/IN_O3") (class "Default")
      (node (ref "DA1") (pin "10") (pinfunction "IN3_10") (pintype "input"))
      (node (ref "R34") (pin "2") (pinfunction "2_2") (pintype "passive"))
    )
    (net (code "56") (name "/IN_O4") (class "Default")
      (node (ref "DA1") (pin "7") (pinfunction "IN2_7") (pintype "input"))
      (node (ref "R31") (pin "2") (pinfunction "2_2") (pintype "passive"))
    )
    (net (code "57") (name "/N$19") (class "Default")
      (node (ref "DA3") (pin "12") (pinfunction "OUT3_12") (pintype "output"))
      (node (ref "IC6") (pin "5") (pinfunction "+IN_5") (pintype "input"))
      (node (ref "R47") (pin "1") (pinfunction "1_1") (pintype "passive"))
    )
    (net (code "58") (name "/OUT1") (class "Default")
      (node (ref "IC3") (pin "7") (pinfunction "OUT_7") (pintype "output"))
      (node (ref "R44") (pin "1") (pinfunction "1_1") (pintype "passive"))
      (node (ref "R59") (pin "1") (pinfunction "1_1") (pintype "passive"))
      (node (ref "R60") (pin "1") (pinfunction "1_1") (pintype "passive"))
    )
    (net (code "59") (name "/OUT2") (class "Default")
      (node (ref "IC3") (pin "1") (pinfunction "OUT_1") (pintype "output"))
      (node (ref "R41") (pin "1") (pinfunction "1_1") (pintype "passive"))
      (node (ref "R53") (pin "1") (pinfunction "1_1") (pintype "passive"))
      (node (ref "R54") (pin "1") (pinfunction "1_1") (pintype "passive"))
    )
    (net (code "60") (name "/OUT3") (class "Default")
      (node (ref "IC5") (pin "7") (pinfunction "OUT_7") (pintype "output"))
      (node (ref "R43") (pin "1") (pinfunction "1_1") (pintype "passive"))
      (node (ref "R57") (pin "1") (pinfunction "1_1") (pintype "passive"))
      (node (ref "R58") (pin "1") (pinfunction "1_1") (pintype "passive"))
    )
    (net (code "61") (name "/OUT4") (class "Default")
      (node (ref "IC5") (pin "1") (pinfunction "OUT_1") (pintype "output"))
      (node (ref "R42") (pin "1") (pinfunction "1_1") (pintype "passive"))
      (node (ref "R55") (pin "1") (pinfunction "1_1") (pintype "passive"))
      (node (ref "R56") (pin "1") (pinfunction "1_1") (pintype "passive"))
    )
    (net (code "62") (name "/OUT5") (class "Default")
      (node (ref "IC2") (pin "1") (pinfunction "OUT_1") (pintype "output"))
      (node (ref "R48") (pin "1") (pinfunction "1_1") (pintype "passive"))
      (node (ref "R67") (pin "1") (pinfunction "1_1") (pintype "passive"))
      (node (ref "R68") (pin "1") (pinfunction "1_1") (pintype "passive"))
    )
    (net (code "63") (name "/OUT6") (class "Default")
      (node (ref "IC2") (pin "14") (pinfunction "OUT_14") (pintype "output"))
      (node (ref "R45") (pin "1") (pinfunction "1_1") (pintype "passive"))
      (node (ref "R61") (pin "1") (pinfunction "1_1") (pintype "passive"))
      (node (ref "R62") (pin "1") (pinfunction "1_1") (pintype "passive"))
    )
    (net (code "64") (name "/OUT7") (class "Default")
      (node (ref "IC6") (pin "6") (pinfunction "-IN_6") (pintype "input"))
      (node (ref "IC6") (pin "7") (pinfunction "OUT_7") (pintype "output"))
      (node (ref "R65") (pin "1") (pinfunction "1_1") (pintype "passive"))
      (node (ref "R66") (pin "1") (pinfunction "1_1") (pintype "passive"))
    )
    (net (code "65") (name "/OUT8") (class "Default")
      (node (ref "IC6") (pin "1") (pinfunction "OUT_1") (pintype "output"))
      (node (ref "IC6") (pin "2") (pinfunction "-IN_2") (pintype "input"))
      (node (ref "R63") (pin "1") (pinfunction "1_1") (pintype "passive"))
      (node (ref "R64") (pin "1") (pinfunction "1_1") (pintype "passive"))
    )
    (net (code "66") (name "/OUT_A") (class "Default")
      (node (ref "IC2") (pin "7") (pinfunction "OUT_7") (pintype "output"))
      (node (ref "R52") (pin "1") (pinfunction "1_1") (pintype "passive"))
      (node (ref "SV4") (pin "2") (pinfunction "2_2") (pintype "passive"))
    )
    (net (code "67") (name "/OUT_B") (class "Default")
      (node (ref "IC2") (pin "8") (pinfunction "OUT_8") (pintype "output"))
      (node (ref "R50") (pin "1") (pinfunction "1_1") (pintype "passive"))
      (node (ref "SV4") (pin "3") (pinfunction "3_3") (pintype "passive"))
    )
    (net (code "68") (name "/SCL") (class "Default")
      (node (ref "IC1") (pin "22") (pinfunction "SCL_22") (pintype "bidirectional"))
      (node (ref "SV33") (pin "3") (pinfunction "3_3") (pintype "passive"))
    )
    (net (code "69") (name "/SDA") (class "Default")
      (node (ref "IC1") (pin "23") (pinfunction "SDA_23") (pintype "bidirectional"))
      (node (ref "SV33") (pin "2") (pinfunction "2_2") (pintype "passive"))
    )
    (net (code "70") (name "/SUM1") (class "Default")
      (node (ref "DA2") (pin "15") (pinfunction "IN4_15") (pintype "input"))
      (node (ref "R13") (pin "2") (pinfunction "2_2") (pintype "passive"))
    )
    (net (code "71") (name "/SUM2") (class "Default")
      (node (ref "DA2") (pin "2") (pinfunction "IN1_2") (pintype "input"))
      (node (ref "R4") (pin "2") (pinfunction "2_2") (pintype "passive"))
    )
    (net (code "72") (name "/SUM3") (class "Default")
      (node (ref "DA2") (pin "10") (pinfunction "IN3_10") (pintype "input"))
      (node (ref "R10") (pin "2") (pinfunction "2_2") (pintype "passive"))
    )
    (net (code "73") (name "/SUM4") (class "Default")
      (node (ref "DA2") (pin "7") (pinfunction "IN2_7") (pintype "input"))
      (node (ref "R7") (pin "2") (pinfunction "2_2") (pintype "passive"))
    )
    (net (code "74") (name "/SUM5") (class "Default")
      (node (ref "DA3") (pin "15") (pinfunction "IN4_15") (pintype "input"))
      (node (ref "R25") (pin "2") (pinfunction "2_2") (pintype "passive"))
    )
    (net (code "75") (name "/SUM6") (class "Default")
      (node (ref "DA3") (pin "2") (pinfunction "IN1_2") (pintype "input"))
      (node (ref "R16") (pin "2") (pinfunction "2_2") (pintype "passive"))
    )
    (net (code "76") (name "/SUM7") (class "Default")
      (node (ref "DA3") (pin "10") (pinfunction "IN3_10") (pintype "input"))
      (node (ref "R22") (pin "2") (pinfunction "2_2") (pintype "passive"))
    )
    (net (code "77") (name "/SUM8") (class "Default")
      (node (ref "DA3") (pin "7") (pinfunction "IN2_7") (pintype "input"))
      (node (ref "R19") (pin "2") (pinfunction "2_2") (pintype "passive"))
    )
    (net (code "78") (name "/SUM_A") (class "Default")
      (node (ref "C24") (pin "2") (pinfunction "2_2") (pintype "passive"))
      (node (ref "IC4") (pin "1") (pinfunction "OUT_1") (pintype "output"))
      (node (ref "R37") (pin "1") (pinfunction "1_1") (pintype "passive"))
      (node (ref "R79") (pin "2") (pinfunction "2_2") (pintype "passive"))
      (node (ref "SV1") (pin "6") (pinfunction "6_6") (pintype "passive"))
    )
    (net (code "79") (name "/SUM_B") (class "Default")
      (node (ref "C25") (pin "2") (pinfunction "2_2") (pintype "passive"))
      (node (ref "IC4") (pin "14") (pinfunction "OUT_14") (pintype "output"))
      (node (ref "R28") (pin "1") (pinfunction "1_1") (pintype "passive"))
      (node (ref "R80") (pin "2") (pinfunction "2_2") (pintype "passive"))
      (node (ref "SV1") (pin "7") (pinfunction "7_7") (pintype "passive"))
    )
    (net (code "80") (name "/SUM_FX_A") (class "Default")
      (node (ref "C26") (pin "2") (pinfunction "2_2") (pintype "passive"))
      (node (ref "IC4") (pin "7") (pinfunction "OUT_7") (pintype "output"))
      (node (ref "R34") (pin "1") (pinfunction "1_1") (pintype "passive"))
      (node (ref "R81") (pin "2") (pinfunction "2_2") (pintype "passive"))
    )
    (net (code "81") (name "/SUM_FX_B") (class "Default")
      (node (ref "C27") (pin "2") (pinfunction "2_2") (pintype "passive"))
      (node (ref "IC4") (pin "8") (pinfunction "OUT_8") (pintype "output"))
      (node (ref "R31") (pin "1") (pinfunction "1_1") (pintype "passive"))
      (node (ref "R82") (pin "2") (pinfunction "2_2") (pintype "passive"))
    )
    (net (code "82") (name "/SW1A") (class "Default")
      (node (ref "IC8") (pin "2") (pinfunction "D_2") (pintype "bidirectional"))
      (node (ref "R59") (pin "2") (pinfunction "2_2") (pintype "passive"))
    )
    (net (code "83") (name "/SW1B") (class "Default")
      (node (ref "IC8") (pin "15") (pinfunction "D_15") (pintype "bidirectional"))
      (node (ref "R60") (pin "2") (pinfunction "2_2") (pintype "passive"))
    )
    (net (code "84") (name "/SW2A") (class "Default")
      (node (ref "IC8") (pin "7") (pinfunction "D_7") (pintype "bidirectional"))
      (node (ref "R53") (pin "2") (pinfunction "2_2") (pintype "passive"))
    )
    (net (code "85") (name "/SW2B") (class "Default")
      (node (ref "IC8") (pin "10") (pinfunction "D_10") (pintype "bidirectional"))
      (node (ref "R54") (pin "2") (pinfunction "2_2") (pintype "passive"))
    )
    (net (code "86") (name "/SW3A") (class "Default")
      (node (ref "IC9") (pin "2") (pinfunction "D_2") (pintype "bidirectional"))
      (node (ref "R57") (pin "2") (pinfunction "2_2") (pintype "passive"))
    )
    (net (code "87") (name "/SW3B") (class "Default")
      (node (ref "IC9") (pin "15") (pinfunction "D_15") (pintype "bidirectional"))
      (node (ref "R58") (pin "2") (pinfunction "2_2") (pintype "passive"))
    )
    (net (code "88") (name "/SW4A") (class "Default")
      (node (ref "IC9") (pin "7") (pinfunction "D_7") (pintype "bidirectional"))
      (node (ref "R55") (pin "2") (pinfunction "2_2") (pintype "passive"))
    )
    (net (code "89") (name "/SW4B") (class "Default")
      (node (ref "IC9") (pin "10") (pinfunction "D_10") (pintype "bidirectional"))
      (node (ref "R56") (pin "2") (pinfunction "2_2") (pintype "passive"))
    )
    (net (code "90") (name "/SW5A") (class "Default")
      (node (ref "IC10") (pin "2") (pinfunction "D_2") (pintype "bidirectional"))
      (node (ref "R67") (pin "2") (pinfunction "2_2") (pintype "passive"))
    )
    (net (code "91") (name "/SW5B") (class "Default")
      (node (ref "IC10") (pin "15") (pinfunction "D_15") (pintype "bidirectional"))
      (node (ref "R68") (pin "2") (pinfunction "2_2") (pintype "passive"))
    )
    (net (code "92") (name "/SW6A") (class "Default")
      (node (ref "IC10") (pin "7") (pinfunction "D_7") (pintype "bidirectional"))
      (node (ref "R61") (pin "2") (pinfunction "2_2") (pintype "passive"))
    )
    (net (code "93") (name "/SW6B") (class "Default")
      (node (ref "IC10") (pin "10") (pinfunction "D_10") (pintype "bidirectional"))
      (node (ref "R62") (pin "2") (pinfunction "2_2") (pintype "passive"))
    )
    (net (code "94") (name "/SW7A") (class "Default")
      (node (ref "IC11") (pin "2") (pinfunction "D_2") (pintype "bidirectional"))
      (node (ref "R65") (pin "2") (pinfunction "2_2") (pintype "passive"))
    )
    (net (code "95") (name "/SW7B") (class "Default")
      (node (ref "IC11") (pin "15") (pinfunction "D_15") (pintype "bidirectional"))
      (node (ref "R66") (pin "2") (pinfunction "2_2") (pintype "passive"))
    )
    (net (code "96") (name "/SW8A") (class "Default")
      (node (ref "IC11") (pin "7") (pinfunction "D_7") (pintype "bidirectional"))
      (node (ref "R63") (pin "2") (pinfunction "2_2") (pintype "passive"))
    )
    (net (code "97") (name "/SW8B") (class "Default")
      (node (ref "IC11") (pin "10") (pinfunction "D_10") (pintype "bidirectional"))
      (node (ref "R64") (pin "2") (pinfunction "2_2") (pintype "passive"))
    )
    (net (code "98") (name "/VL") (class "Default")
      (node (ref "IC10") (pin "12") (pinfunction "VL_12") (pintype "bidirectional"))
      (node (ref "IC11") (pin "12") (pinfunction "VL_12") (pintype "bidirectional"))
      (node (ref "IC8") (pin "12") (pinfunction "VL_12") (pintype "bidirectional"))
      (node (ref "IC9") (pin "12") (pinfunction "VL_12") (pintype "bidirectional"))
      (node (ref "R77") (pin "2") (pinfunction "2_2") (pintype "passive"))
      (node (ref "R78") (pin "1") (pinfunction "1_1") (pintype "passive"))
    )
    (net (code "99") (name "/~{RST}") (class "Default")
      (node (ref "IC1") (pin "3") (pinfunction "~{RESET}_3") (pintype "bidirectional"))
      (node (ref "R1") (pin "2") (pinfunction "2_2") (pintype "passive"))
      (node (ref "SV33") (pin "5") (pinfunction "5_5") (pintype "passive"))
    )
    (net (code "100") (name "DGND") (class "Default")
      (node (ref "C23") (pin "1") (pinfunction "1_1") (pintype "passive"))
      (node (ref "IC1") (pin "12") (pinfunction "VSS_12") (pintype "power_in"))
      (node (ref "IC1") (pin "2") (pinfunction "A1_2") (pintype "bidirectional"))
      (node (ref "IC1") (pin "21") (pinfunction "A0_21") (pintype "bidirectional"))
      (node (ref "SV33") (pin "4") (pinfunction "4_4") (pintype "passive"))
    )
    (net (code "101") (name "GND") (class "Default")
      (node (ref "C1") (pin "1") (pinfunction "1_1") (pintype "passive"))
      (node (ref "C10") (pin "2") (pinfunction "2_2") (pintype "passive"))
      (node (ref "C11") (pin "1") (pinfunction "1_1") (pintype "passive"))
      (node (ref "C12") (pin "2") (pinfunction "2_2") (pintype "passive"))
      (node (ref "C13") (pin "1") (pinfunction "1_1") (pintype "passive"))
      (node (ref "C14") (pin "1") (pinfunction "1_1") (pintype "passive"))
      (node (ref "C15") (pin "1") (pinfunction "1_1") (pintype "passive"))
      (node (ref "C16") (pin "1") (pinfunction "1_1") (pintype "passive"))
      (node (ref "C17") (pin "2") (pinfunction "2_2") (pintype "passive"))
      (node (ref "C2") (pin "2") (pinfunction "2_2") (pintype "passive"))
      (node (ref "C3") (pin "1") (pinfunction "1_1") (pintype "passive"))
      (node (ref "C4") (pin "2") (pinfunction "2_2") (pintype "passive"))
      (node (ref "C5") (pin "1") (pinfunction "1_1") (pintype "passive"))
      (node (ref "C6") (pin "2") (pinfunction "2_2") (pintype "passive"))
      (node (ref "C7") (pin "1") (pinfunction "1_1") (pintype "passive"))
      (node (ref "C8") (pin "2") (pinfunction "2_2") (pintype "passive"))
      (node (ref "C9") (pin "1") (pinfunction "1_1") (pintype "passive"))
      (node (ref "DA1") (pin "8") (pinfunction "GND_8") (pintype "power_in"))
      (node (ref "DA2") (pin "8") (pinfunction "GND_8") (pintype "power_in"))
      (node (ref "DA3") (pin "8") (pinfunction "GND_8") (pintype "power_in"))
      (node (ref "IC10") (pin "5") (pinfunction "AGND_5") (pintype "power_in"))
      (node (ref "IC11") (pin "5") (pinfunction "AGND_5") (pintype "power_in"))
      (node (ref "IC2") (pin "12") (pinfunction "+IN_12") (pintype "input"))
      (node (ref "IC2") (pin "3") (pinfunction "+IN_3") (pintype "input"))
      (node (ref "IC3") (pin "3") (pinfunction "+IN_3") (pintype "input"))
      (node (ref "IC3") (pin "5") (pinfunction "+IN_5") (pintype "input"))
      (node (ref "IC4") (pin "10") (pinfunction "+IN_10") (pintype "input"))
      (node (ref "IC4") (pin "12") (pinfunction "+IN_12") (pintype "input"))
      (node (ref "IC4") (pin "3") (pinfunction "+IN_3") (pintype "input"))
      (node (ref "IC4") (pin "5") (pinfunction "+IN_5") (pintype "input"))
      (node (ref "IC5") (pin "3") (pinfunction "+IN_3") (pintype "input"))
      (node (ref "IC5") (pin "5") (pinfunction "+IN_5") (pintype "input"))
      (node (ref "IC8") (pin "5") (pinfunction "AGND_5") (pintype "power_in"))
      (node (ref "IC9") (pin "5") (pinfunction "AGND_5") (pintype "power_in"))
      (node (ref "R12") (pin "1") (pinfunction "1_1") (pintype "passive"))
      (node (ref "R15") (pin "1") (pinfunction "1_1") (pintype "passive"))
      (node (ref "R18") (pin "1") (pinfunction "1_1") (pintype "passive"))
      (node (ref "R21") (pin "1") (pinfunction "1_1") (pintype "passive"))
      (node (ref "R24") (pin "1") (pinfunction "1_1") (pintype "passive"))
      (node (ref "R27") (pin "1") (pinfunction "1_1") (pintype "passive"))
      (node (ref "R3") (pin "1") (pinfunction "1_1") (pintype "passive"))
      (node (ref "R30") (pin "1") (pinfunction "1_1") (pintype "passive"))
      (node (ref "R33") (pin "1") (pinfunction "1_1") (pintype "passive"))
      (node (ref "R36") (pin "1") (pinfunction "1_1") (pintype "passive"))
      (node (ref "R46") (pin "2") (pinfunction "2_2") (pintype "passive"))
      (node (ref "R47") (pin "2") (pinfunction "2_2") (pintype "passive"))
      (node (ref "R49") (pin "2") (pinfunction "2_2") (pintype "passive"))
      (node (ref "R51") (pin "2") (pinfunction "2_2") (pintype "passive"))
      (node (ref "R6") (pin "1") (pinfunction "1_1") (pintype "passive"))
      (node (ref "R73") (pin "1") (pinfunction "1_1") (pintype "passive"))
      (node (ref "R74") (pin "1") (pinfunction "1_1") (pintype "passive"))
      (node (ref "R75") (pin "1") (pinfunction "1_1") (pintype "passive"))
      (node (ref "R76") (pin "1") (pinfunction "1_1") (pintype "passive"))
      (node (ref "R78") (pin "2") (pinfunction "2_2") (pintype "passive"))
      (node (ref "R9") (pin "1") (pinfunction "1_1") (pintype "passive"))
      (node (ref "SV4") (pin "7") (pinfunction "7_7") (pintype "passive"))
    )
    (net (code "102") (name "Net-(C13-Pad2)") (class "Default")
      (node (ref "C13") (pin "2") (pinfunction "2_2") (pintype "passive"))
      (node (ref "R38") (pin "1") (pinfunction "1_1") (pintype "passive"))
    )
    (net (code "103") (name "Net-(C14-Pad2)") (class "Default")
      (node (ref "C14") (pin "2") (pinfunction "2_2") (pintype "passive"))
      (node (ref "R39") (pin "1") (pinfunction "1_1") (pintype "passive"))
    )
    (net (code "104") (name "Net-(C15-Pad2)") (class "Default")
      (node (ref "C15") (pin "2") (pinfunction "2_2") (pintype "passive"))
      (node (ref "R40") (pin "1") (pinfunction "1_1") (pintype "passive"))
    )
    (net (code "105") (name "Net-(DA1B-CV2)") (class "Default")
      (node (ref "DA1") (pin "6") (pinfunction "CV2_6") (pintype "input"))
      (node (ref "R29") (pin "2") (pinfunction "2_2") (pintype "passive"))
      (node (ref "R30") (pin "2") (pinfunction "2_2") (pintype "passive"))
    )
    (net (code "106") (name "Net-(DA1B-CV3)") (class "Default")
      (node (ref "DA1") (pin "11") (pinfunction "CV3_11") (pintype "input"))
      (node (ref "R32") (pin "2") (pinfunction "2_2") (pintype "passive"))
      (node (ref "R33") (pin "2") (pinfunction "2_2") (pintype "passive"))
    )
    (net (code "107") (name "Net-(DA1B-CV4)") (class "Default")
      (node (ref "DA1") (pin "14") (pinfunction "CV4_14") (pintype "input"))
      (node (ref "R35") (pin "2") (pinfunction "2_2") (pintype "passive"))
      (node (ref "R36") (pin "2") (pinfunction "2_2") (pintype "passive"))
    )
    (net (code "108") (name "Net-(DA1B-OUT1)") (class "Default")
      (node (ref "DA1") (pin "4") (pinfunction "OUT1_4") (pintype "output"))
      (node (ref "IC2") (pin "10") (pinfunction "+IN_10") (pintype "input"))
      (node (ref "R51") (pin "1") (pinfunction "1_1") (pintype "passive"))
    )
    (net (code "109") (name "Net-(DA1B-OUT2)") (class "Default")
      (node (ref "DA1") (pin "5") (pinfunction "OUT2_5") (pintype "output"))
      (node (ref "IC2") (pin "9") (pinfunction "-IN_9") (pintype "input"))
      (node (ref "R50") (pin "2") (pinfunction "2_2") (pintype "passive"))
    )
    (net (code "110") (name "Net-(DA1B-OUT3)") (class "Default")
      (node (ref "DA1") (pin "12") (pinfunction "OUT3_12") (pintype "output"))
      (node (ref "IC2") (pin "6") (pinfunction "-IN_6") (pintype "input"))
      (node (ref "R52") (pin "2") (pinfunction "2_2") (pintype "passive"))
    )
    (net (code "111") (name "Net-(DA1B-OUT4)") (class "Default")
      (node (ref "DA1") (pin "13") (pinfunction "OUT4_13") (pintype "output"))
      (node (ref "IC2") (pin "5") (pinfunction "+IN_5") (pintype "input"))
      (node (ref "R49") (pin "1") (pinfunction "1_1") (pintype "passive"))
    )
    (net (code "112") (name "Net-(DA1B-VREF)") (class "Default")
      (node (ref "DA1") (pin "1") (pinfunction "VREF_1") (pintype "output"))
      (node (ref "R40") (pin "2") (pinfunction "2_2") (pintype "passive"))
    )
    (net (code "113") (name "Net-(DA2B-CV2)") (class "Default")
      (node (ref "DA2") (pin "6") (pinfunction "CV2_6") (pintype "input"))
      (node (ref "R5") (pin "2") (pinfunction "2_2") (pintype "passive"))
      (node (ref "R6") (pin "2") (pinfunction "2_2") (pintype "passive"))
    )
    (net (code "114") (name "Net-(DA2B-CV3)") (class "Default")
      (node (ref "DA2") (pin "11") (pinfunction "CV3_11") (pintype "input"))
      (node (ref "R8") (pin "2") (pinfunction "2_2") (pintype "passive"))
      (node (ref "R9") (pin "2") (pinfunction "2_2") (pintype "passive"))
    )
    (net (code "115") (name "Net-(DA2B-CV4)") (class "Default")
      (node (ref "DA2") (pin "14") (pinfunction "CV4_14") (pintype "input"))
      (node (ref "R11") (pin "2") (pinfunction "2_2") (pintype "passive"))
      (node (ref "R12") (pin "2") (pinfunction "2_2") (pintype "passive"))
    )
    (net (code "116") (name "Net-(DA2B-VREF)") (class "Default")
      (node (ref "DA2") (pin "1") (pinfunction "VREF_1") (pintype "output"))
      (node (ref "R38") (pin "2") (pinfunction "2_2") (pintype "passive"))
    )
    (net (code "117") (name "Net-(DA3B-CV2)") (class "Default")
      (node (ref "DA3") (pin "6") (pinfunction "CV2_6") (pintype "input"))
      (node (ref "R17") (pin "2") (pinfunction "2_2") (pintype "passive"))
      (node (ref "R18") (pin "2") (pinfunction "2_2") (pintype "passive"))
    )
    (net (code "118") (name "Net-(DA3B-CV3)") (class "Default")
      (node (ref "DA3") (pin "11") (pinfunction "CV3_11") (pintype "input"))
      (node (ref "R20") (pin "2") (pinfunction "2_2") (pintype "passive"))
      (node (ref "R21") (pin "2") (pinfunction "2_2") (pintype "passive"))
    )
    (net (code "119") (name "Net-(DA3B-CV4)") (class "Default")
      (node (ref "DA3") (pin "14") (pinfunction "CV4_14") (pintype "input"))
      (node (ref "R23") (pin "2") (pinfunction "2_2") (pintype "passive"))
      (node (ref "R24") (pin "2") (pinfunction "2_2") (pintype "passive"))
    )
    (net (code "120") (name "Net-(DA3B-OUT2)") (class "Default")
      (node (ref "DA3") (pin "5") (pinfunction "OUT2_5") (pintype "output"))
      (node (ref "IC6") (pin "3") (pinfunction "+IN_3") (pintype "input"))
      (node (ref "R46") (pin "1") (pinfunction "1_1") (pintype "passive"))
    )
    (net (code "121") (name "Net-(DA3B-VREF)") (class "Default")
      (node (ref "DA3") (pin "1") (pinfunction "VREF_1") (pintype "output"))
      (node (ref "R39") (pin "2") (pinfunction "2_2") (pintype "passive"))
    )
    (net (code "122") (name "unconnected-(IC1-~{INT}-Pad1)") (class "Default")
      (node (ref "IC1") (pin "1") (pinfunction "~{INT}_1") (pintype "bidirectional"))
    )
  )
)
